# Power.net
KiCad netlist of a schematic drawn in Altium Designer
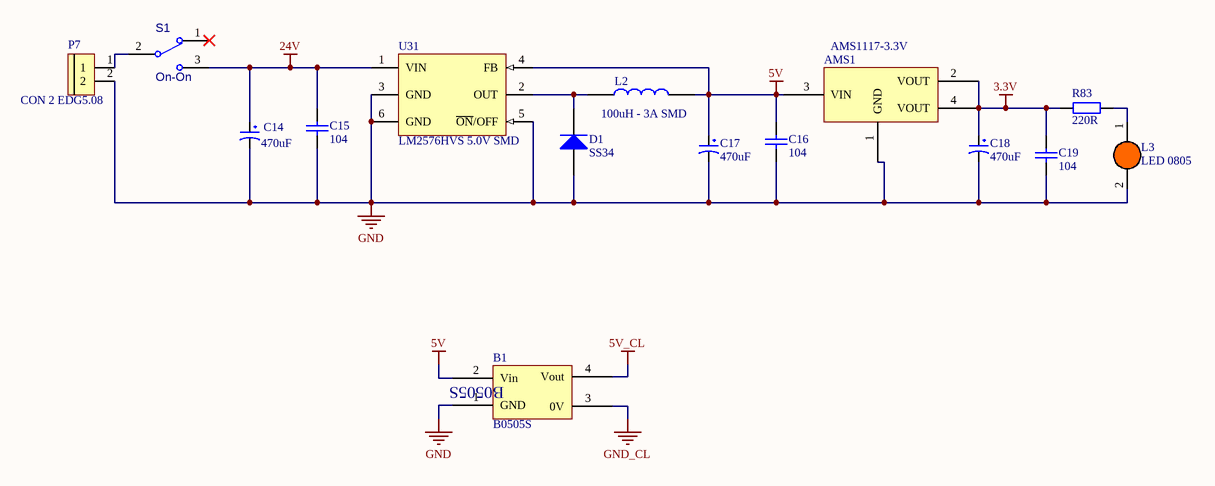
[diagram p0: Power.SchDoc]

(export (version "E")
  (design (tool "Eeschema 10.0.6"))
  (components
    (comp (ref "AMS1")
      (value "AMS1117-3.3V")
      (footprint "SOT223")
      (description "Dán")
      (libsource (lib "Altium_Lib_by_KhueNguyenCreator") (part "AMS1117 SMD"))
    )
    (comp (ref "B1")
      (value "B0505S")
      (footprint "B0505S")
      (description "Cắm")
      (libsource (lib "Altium_Lib_by_KhueNguyenCreator") (part "B0505S"))
    )
    (comp (ref "C14")
      (value "470uF")
      (footprint "tu hoa 10mm")
      (description "Cắm")
      (libsource (lib "Altium_Lib_by_KhueNguyenCreator") (part "Tu Hoa 470uF 50V 10x17"))
    )
    (comp (ref "C15")
      (value "104")
      (footprint "tu 0805")
      (description "Dán")
      (libsource (lib "Altium_Lib_by_KhueNguyenCreator") (part "Tu 0805 104 50V 10%"))
    )
    (comp (ref "C16")
      (value "104")
      (footprint "tu 0805")
      (description "Dán")
      (libsource (lib "Altium_Lib_by_KhueNguyenCreator") (part "Tu 0805 104 50V 10%"))
    )
    (comp (ref "C17")
      (value "470uF")
      (footprint "tu hoa 8mm")
      (description "Cắm")
      (libsource (lib "Altium_Lib_by_KhueNguyenCreator") (part "Tu Hoa 470uF 16V 8x11"))
    )
    (comp (ref "C18")
      (value "470uF")
      (footprint "tu hoa 8mm")
      (description "Cắm")
      (libsource (lib "Altium_Lib_by_KhueNguyenCreator") (part "Tu Hoa 470uF 16V 8x11"))
    )
    (comp (ref "C19")
      (value "104")
      (footprint "tu 0805")
      (description "Dán")
      (libsource (lib "Altium_Lib_by_KhueNguyenCreator") (part "Tu 0805 104 50V 10%"))
    )
    (comp (ref "D1")
      (value "SS34")
      (footprint "DIODE SMA")
      (description "Dán")
      (libsource (lib "Altium_Lib_by_KhueNguyenCreator") (part "Diode SS34 ( 1N5822 )"))
    )
    (comp (ref "L2")
      (value "100uH - 3A SMD")
      (footprint "Cuon Cam 12x12x10")
      (description "Dán")
      (libsource (lib "Altium_Lib_by_KhueNguyenCreator") (part "CUON CAM 100uH SMD"))
    )
    (comp (ref "L3")
      (value "LED 0805")
      (footprint "LED-0805-Orange")
      (description "Dán")
      (libsource (lib "Altium_Lib_by_KhueNguyenCreator") (part "LED 0805 Cam"))
    )
    (comp (ref "P7")
      (value "CON 2 EDG5.08")
      (footprint "CON 2 2EDG5.08")
      (description "Cắm")
      (libsource (lib "Altium_Lib_by_KhueNguyenCreator") (part "CON 2 EDG5.08"))
    )
    (comp (ref "R83")
      (value "220R")
      (footprint "tro smd 0805")
      (description "Dán")
      (libsource (lib "Altium_Lib_by_KhueNguyenCreator") (part "Tro 0805 5% 220R"))
    )
    (comp (ref "S1")
      (value "ON-ON")
      (footprint "SWITCH_SPDT_SLIDER")
      (description "Switch THD vertical toggle SPDT")
      (fields (field (name "SWITCH FUNCTION") "On-On"))
      (libsource (lib "My library altium") (part "SW_THD_SPDT_On-On"))
    )
    (comp (ref "U31")
      (value "LM2576HVS 5.0V SMD")
      (footprint "TO263-5")
      (description "Dán")
      (libsource (lib "Altium_Lib_by_KhueNguyenCreator") (part "LM2576HVS 5.0V SMD"))
    )
  )
  (nets
    (net (code "1") (name "3.3V") (class "Default")
      (node (ref "AMS1") (pin "2") (pinfunction "VOUT_2") (pintype "passive"))
      (node (ref "AMS1") (pin "4") (pinfunction "VOUT_4") (pintype "passive"))
      (node (ref "C18") (pin "1") (pinfunction "1_1") (pintype "passive"))
      (node (ref "C19") (pin "1") (pinfunction "1_1") (pintype "passive"))
      (node (ref "R83") (pin "1") (pinfunction "1_1") (pintype "passive"))
    )
    (net (code "2") (name "5V") (class "Default")
      (node (ref "AMS1") (pin "3") (pinfunction "VIN_3") (pintype "passive"))
      (node (ref "B1") (pin "2") (pinfunction "Vin_2") (pintype "passive"))
      (node (ref "C16") (pin "1") (pinfunction "1_1") (pintype "passive"))
      (node (ref "C17") (pin "1") (pinfunction "1_1") (pintype "passive"))
      (node (ref "L2") (pin "2") (pinfunction "2_2") (pintype "passive"))
      (node (ref "U31") (pin "4") (pinfunction "FB_4") (pintype "input"))
    )
    (net (code "3") (name "5V_CL") (class "Default")
      (node (ref "B1") (pin "4") (pinfunction "Vout_4") (pintype "passive"))
    )
    (net (code "4") (name "24V") (class "Default")
      (node (ref "C14") (pin "1") (pinfunction "1_1") (pintype "passive"))
      (node (ref "C15") (pin "2") (pinfunction "2_2") (pintype "passive"))
      (node (ref "S1") (pin "3") (pinfunction "3_3") (pintype "passive"))
      (node (ref "U31") (pin "1") (pinfunction "VIN_1") (pintype "power_in"))
    )
    (net (code "5") (name "GND") (class "Default")
      (node (ref "AMS1") (pin "1") (pinfunction "GND_1") (pintype "passive"))
      (node (ref "B1") (pin "1") (pinfunction "GND_1") (pintype "passive"))
      (node (ref "C14") (pin "2") (pinfunction "2_2") (pintype "passive"))
      (node (ref "C15") (pin "1") (pinfunction "1_1") (pintype "passive"))
      (node (ref "C16") (pin "2") (pinfunction "2_2") (pintype "passive"))
      (node (ref "C17") (pin "2") (pinfunction "2_2") (pintype "passive"))
      (node (ref "C18") (pin "2") (pinfunction "2_2") (pintype "passive"))
      (node (ref "C19") (pin "2") (pinfunction "2_2") (pintype "passive"))
      (node (ref "D1") (pin "1") (pinfunction "A_1") (pintype "passive"))
      (node (ref "L3") (pin "2") (pinfunction "K_2") (pintype "passive"))
      (node (ref "P7") (pin "2") (pinfunction "2_2") (pintype "passive"))
      (node (ref "U31") (pin "3") (pinfunction "GND_3") (pintype "power_in"))
      (node (ref "U31") (pin "5") (pinfunction "~{ON}/OFF_5") (pintype "input"))
      (node (ref "U31") (pin "6") (pinfunction "GND_6") (pintype "passive"))
    )
    (net (code "6") (name "GND_CL") (class "Default")
      (node (ref "B1") (pin "3") (pinfunction "0V_3") (pintype "passive"))
    )
    (net (code "7") (name "Net-(D1-K)") (class "Default")
      (node (ref "D1") (pin "2") (pinfunction "K_2") (pintype "passive"))
      (node (ref "L2") (pin "1") (pinfunction "1_1") (pintype "passive"))
      (node (ref "U31") (pin "2") (pinfunction "OUT_2") (pintype "power_in"))
    )
    (net (code "8") (name "Net-(L3-A)") (class "Default")
      (node (ref "L3") (pin "1") (pinfunction "A_1") (pintype "passive"))
      (node (ref "R83") (pin "2") (pinfunction "2_2") (pintype "passive"))
    )
    (net (code "9") (name "Net-(P7-Pad1)") (class "Default")
      (node (ref "P7") (pin "1") (pinfunction "1_1") (pintype "passive"))
      (node (ref "S1") (pin "2") (pinfunction "2_2") (pintype "passive"))
    )
    (net (code "10") (name "unconnected-(S1-Pad1)") (class "Default")
      (node (ref "S1") (pin "1") (pinfunction "1_1") (pintype "passive+no_connect"))
    )
  )
)
